# ContunityTestingRig.net
KiCad netlist of a schematic drawn in EAGLE
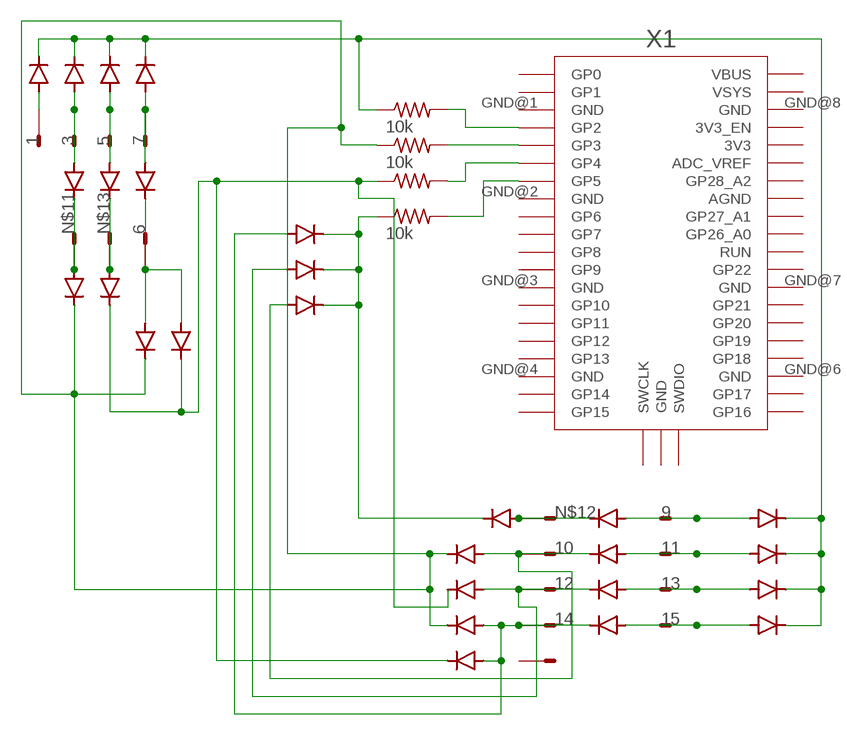
[diagram p0: schematic, sheet 1]

(export (version "E")
  (design (tool "Eeschema 10.0.6"))
  (components
    (comp (ref "D1")
      (value "SCHOTTKY")
      (footprint "eagle-import:MINI-SMA")
      (libsource (lib "eagle-import") (part "DIODE_SCHOTTKY_CDBM1100-G"))
    )
    (comp (ref "D2")
      (value "SCHOTTKY")
      (footprint "eagle-import:MINI-SMA")
      (libsource (lib "eagle-import") (part "DIODE_SCHOTTKY_CDBM1100-G"))
    )
    (comp (ref "D3")
      (value "SCHOTTKY")
      (footprint "eagle-import:MINI-SMA")
      (libsource (lib "eagle-import") (part "DIODE_SCHOTTKY_CDBM1100-G"))
    )
    (comp (ref "D4")
      (value "SCHOTTKY")
      (footprint "eagle-import:MINI-SMA")
      (libsource (lib "eagle-import") (part "DIODE_SCHOTTKY_CDBM1100-G"))
    )
    (comp (ref "D5")
      (value "SCHOTTKY")
      (footprint "eagle-import:MINI-SMA")
      (libsource (lib "eagle-import") (part "DIODE_SCHOTTKY_CDBM1100-G"))
    )
    (comp (ref "D6")
      (value "SCHOTTKY")
      (footprint "eagle-import:MINI-SMA")
      (libsource (lib "eagle-import") (part "DIODE_SCHOTTKY_CDBM1100-G"))
    )
    (comp (ref "D7")
      (value "SCHOTTKY")
      (footprint "eagle-import:MINI-SMA")
      (libsource (lib "eagle-import") (part "DIODE_SCHOTTKY_CDBM1100-G"))
    )
    (comp (ref "D8")
      (value "SCHOTTKY")
      (footprint "eagle-import:MINI-SMA")
      (libsource (lib "eagle-import") (part "DIODE_SCHOTTKY_CDBM1100-G"))
    )
    (comp (ref "D9")
      (value "SCHOTTKY")
      (footprint "eagle-import:MINI-SMA")
      (libsource (lib "eagle-import") (part "DIODE_SCHOTTKY_CDBM1100-G"))
    )
    (comp (ref "D10")
      (value "SCHOTTKY")
      (footprint "eagle-import:MINI-SMA")
      (libsource (lib "eagle-import") (part "DIODE_SCHOTTKY_CDBM1100-G"))
    )
    (comp (ref "D11")
      (value "SCHOTTKY")
      (footprint "eagle-import:MINI-SMA")
      (libsource (lib "eagle-import") (part "DIODE_SCHOTTKY_CDBM1100-G"))
    )
    (comp (ref "D12")
      (value "SCHOTTKY")
      (footprint "eagle-import:MINI-SMA")
      (libsource (lib "eagle-import") (part "DIODE_SCHOTTKY_CDBM1100-G"))
    )
    (comp (ref "D13")
      (value "SCHOTTKY")
      (footprint "eagle-import:MINI-SMA")
      (libsource (lib "eagle-import") (part "DIODE_SCHOTTKY_CDBM1100-G"))
    )
    (comp (ref "D14")
      (value "SCHOTTKY")
      (footprint "eagle-import:MINI-SMA")
      (libsource (lib "eagle-import") (part "DIODE_SCHOTTKY_CDBM1100-G"))
    )
    (comp (ref "D15")
      (value "SCHOTTKY")
      (footprint "eagle-import:MINI-SMA")
      (libsource (lib "eagle-import") (part "DIODE_SCHOTTKY_CDBM1100-G"))
    )
    (comp (ref "D16")
      (value "SCHOTTKY")
      (footprint "eagle-import:MINI-SMA")
      (libsource (lib "eagle-import") (part "DIODE_SCHOTTKY_CDBM1100-G"))
    )
    (comp (ref "D17")
      (value "SCHOTTKY")
      (footprint "eagle-import:MINI-SMA")
      (libsource (lib "eagle-import") (part "DIODE_SCHOTTKY_CDBM1100-G"))
    )
    (comp (ref "D18")
      (value "SCHOTTKY")
      (footprint "eagle-import:MINI-SMA")
      (libsource (lib "eagle-import") (part "DIODE_SCHOTTKY_CDBM1100-G"))
    )
    (comp (ref "D19")
      (value "SCHOTTKY")
      (footprint "eagle-import:MINI-SMA")
      (libsource (lib "eagle-import") (part "DIODE_SCHOTTKY_CDBM1100-G"))
    )
    (comp (ref "D20")
      (value "SCHOTTKY")
      (footprint "eagle-import:MINI-SMA")
      (libsource (lib "eagle-import") (part "DIODE_SCHOTTKY_CDBM1100-G"))
    )
    (comp (ref "D21")
      (value "SCHOTTKY")
      (footprint "eagle-import:MINI-SMA")
      (libsource (lib "eagle-import") (part "DIODE_SCHOTTKY_CDBM1100-G"))
    )
    (comp (ref "D22")
      (value "SCHOTTKY")
      (footprint "eagle-import:MINI-SMA")
      (libsource (lib "eagle-import") (part "DIODE_SCHOTTKY_CDBM1100-G"))
    )
    (comp (ref "D23")
      (value "SCHOTTKY")
      (footprint "eagle-import:MINI-SMA")
      (libsource (lib "eagle-import") (part "DIODE_SCHOTTKY_CDBM1100-G"))
    )
    (comp (ref "D24")
      (value "SCHOTTKY")
      (footprint "eagle-import:MINI-SMA")
      (libsource (lib "eagle-import") (part "DIODE_SCHOTTKY_CDBM1100-G"))
    )
    (comp (ref "D25")
      (value "SCHOTTKY")
      (footprint "eagle-import:MINI-SMA")
      (libsource (lib "eagle-import") (part "DIODE_SCHOTTKY_CDBM1100-G"))
    )
    (comp (ref "D26")
      (value "SCHOTTKY")
      (footprint "eagle-import:MINI-SMA")
      (libsource (lib "eagle-import") (part "DIODE_SCHOTTKY_CDBM1100-G"))
    )
    (comp (ref "D27")
      (value "SCHOTTKY")
      (footprint "eagle-import:MINI-SMA")
      (libsource (lib "eagle-import") (part "DIODE_SCHOTTKY_CDBM1100-G"))
    )
    (comp (ref "R1")
      (value "10k")
      (footprint "eagle-import:R1206FAB")
      (libsource (lib "eagle-import") (part "R1206FAB"))
    )
    (comp (ref "R2")
      (value "10k")
      (footprint "eagle-import:R1206FAB")
      (libsource (lib "eagle-import") (part "R1206FAB"))
    )
    (comp (ref "R3")
      (value "10k")
      (footprint "eagle-import:R1206FAB")
      (libsource (lib "eagle-import") (part "R1206FAB"))
    )
    (comp (ref "R4")
      (value "10k")
      (footprint "eagle-import:R1206FAB")
      (libsource (lib "eagle-import") (part "R1206FAB"))
    )
    (comp (ref "SV1")
      (value "16E")
      (footprint "eagle-import:16P")
      (libsource (lib "eagle-import") (part "16E"))
    )
    (comp (ref "X1")
      (value "RPI_PICO_IG-SMD")
      (footprint "eagle-import:RPI_PICO")
      (libsource (lib "eagle-import") (part "RPI_PICO_IG-SMD"))
    )
  )
  (nets
    (net (code "1") (name "/1") (class "Default")
      (node (ref "D1") (pin "KATHODE") (pinfunction "KATHODE_KATHODE") (pintype "bidirectional"))
      (node (ref "D13") (pin "KATHODE") (pinfunction "KATHODE_KATHODE") (pintype "bidirectional"))
      (node (ref "D14") (pin "KATHODE") (pinfunction "KATHODE_KATHODE") (pintype "bidirectional"))
      (node (ref "D15") (pin "KATHODE") (pinfunction "KATHODE_KATHODE") (pintype "bidirectional"))
      (node (ref "D16") (pin "KATHODE") (pinfunction "KATHODE_KATHODE") (pintype "bidirectional"))
      (node (ref "D2") (pin "KATHODE") (pinfunction "KATHODE_KATHODE") (pintype "bidirectional"))
      (node (ref "D24") (pin "KATHODE") (pinfunction "KATHODE_KATHODE") (pintype "bidirectional"))
      (node (ref "D3") (pin "KATHODE") (pinfunction "KATHODE_KATHODE") (pintype "bidirectional"))
      (node (ref "R1") (pin "1") (pinfunction "1_1") (pintype "passive"))
    )
    (net (code "2") (name "/3") (class "Default")
      (node (ref "D1") (pin "ANODE") (pinfunction "ANODE_ANODE") (pintype "bidirectional"))
      (node (ref "D4") (pin "ANODE") (pinfunction "ANODE_ANODE") (pintype "bidirectional"))
      (node (ref "SV1") (pin "3") (pinfunction "S_3") (pintype "passive"))
    )
    (net (code "3") (name "/5") (class "Default")
      (node (ref "D2") (pin "ANODE") (pinfunction "ANODE_ANODE") (pintype "bidirectional"))
      (node (ref "D5") (pin "ANODE") (pinfunction "ANODE_ANODE") (pintype "bidirectional"))
      (node (ref "SV1") (pin "5") (pinfunction "S_5") (pintype "passive"))
    )
    (net (code "4") (name "/6") (class "Default")
      (node (ref "D6") (pin "KATHODE") (pinfunction "KATHODE_KATHODE") (pintype "bidirectional"))
      (node (ref "D7") (pin "ANODE") (pinfunction "ANODE_ANODE") (pintype "bidirectional"))
      (node (ref "D8") (pin "ANODE") (pinfunction "ANODE_ANODE") (pintype "bidirectional"))
      (node (ref "SV1") (pin "6") (pinfunction "S_6") (pintype "passive"))
    )
    (net (code "5") (name "/7") (class "Default")
      (node (ref "D3") (pin "ANODE") (pinfunction "ANODE_ANODE") (pintype "bidirectional"))
      (node (ref "D6") (pin "ANODE") (pinfunction "ANODE_ANODE") (pintype "bidirectional"))
      (node (ref "SV1") (pin "7") (pinfunction "S_7") (pintype "passive"))
    )
    (net (code "6") (name "/9") (class "Default")
      (node (ref "D13") (pin "ANODE") (pinfunction "ANODE_ANODE") (pintype "bidirectional"))
      (node (ref "D9") (pin "ANODE") (pinfunction "ANODE_ANODE") (pintype "bidirectional"))
      (node (ref "SV1") (pin "9") (pinfunction "S_9") (pintype "passive"))
    )
    (net (code "7") (name "/10") (class "Default")
      (node (ref "D10") (pin "KATHODE") (pinfunction "KATHODE_KATHODE") (pintype "bidirectional"))
      (node (ref "D17") (pin "ANODE") (pinfunction "ANODE_ANODE") (pintype "bidirectional"))
      (node (ref "D23") (pin "ANODE") (pinfunction "ANODE_ANODE") (pintype "bidirectional"))
      (node (ref "SV1") (pin "10") (pinfunction "S_10") (pintype "passive"))
    )
    (net (code "8") (name "/11") (class "Default")
      (node (ref "D10") (pin "ANODE") (pinfunction "ANODE_ANODE") (pintype "bidirectional"))
      (node (ref "D14") (pin "ANODE") (pinfunction "ANODE_ANODE") (pintype "bidirectional"))
      (node (ref "SV1") (pin "11") (pinfunction "S_11") (pintype "passive"))
    )
    (net (code "9") (name "/12") (class "Default")
      (node (ref "D11") (pin "KATHODE") (pinfunction "KATHODE_KATHODE") (pintype "bidirectional"))
      (node (ref "D19") (pin "ANODE") (pinfunction "ANODE_ANODE") (pintype "bidirectional"))
      (node (ref "D22") (pin "ANODE") (pinfunction "ANODE_ANODE") (pintype "bidirectional"))
      (node (ref "SV1") (pin "12") (pinfunction "S_12") (pintype "passive"))
    )
    (net (code "10") (name "/13") (class "Default")
      (node (ref "D11") (pin "ANODE") (pinfunction "ANODE_ANODE") (pintype "bidirectional"))
      (node (ref "D15") (pin "ANODE") (pinfunction "ANODE_ANODE") (pintype "bidirectional"))
      (node (ref "SV1") (pin "13") (pinfunction "S_13") (pintype "passive"))
    )
    (net (code "11") (name "/14") (class "Default")
      (node (ref "D12") (pin "KATHODE") (pinfunction "KATHODE_KATHODE") (pintype "bidirectional"))
      (node (ref "D18") (pin "ANODE") (pinfunction "ANODE_ANODE") (pintype "bidirectional"))
      (node (ref "D20") (pin "ANODE") (pinfunction "ANODE_ANODE") (pintype "bidirectional"))
      (node (ref "D21") (pin "ANODE") (pinfunction "ANODE_ANODE") (pintype "bidirectional"))
      (node (ref "SV1") (pin "14") (pinfunction "S_14") (pintype "passive"))
    )
    (net (code "12") (name "/15") (class "Default")
      (node (ref "D12") (pin "ANODE") (pinfunction "ANODE_ANODE") (pintype "bidirectional"))
      (node (ref "D16") (pin "ANODE") (pinfunction "ANODE_ANODE") (pintype "bidirectional"))
      (node (ref "SV1") (pin "15") (pinfunction "S_15") (pintype "passive"))
    )
    (net (code "13") (name "/N$11") (class "Default")
      (node (ref "D25") (pin "ANODE") (pinfunction "ANODE_ANODE") (pintype "bidirectional"))
      (node (ref "D4") (pin "KATHODE") (pinfunction "KATHODE_KATHODE") (pintype "bidirectional"))
      (node (ref "SV1") (pin "2") (pinfunction "S_2") (pintype "passive"))
    )
    (net (code "14") (name "/N$12") (class "Default")
      (node (ref "D26") (pin "ANODE") (pinfunction "ANODE_ANODE") (pintype "bidirectional"))
      (node (ref "D9") (pin "KATHODE") (pinfunction "KATHODE_KATHODE") (pintype "bidirectional"))
      (node (ref "SV1") (pin "8") (pinfunction "S_8") (pintype "passive"))
    )
    (net (code "15") (name "/N$13") (class "Default")
      (node (ref "D27") (pin "ANODE") (pinfunction "ANODE_ANODE") (pintype "bidirectional"))
      (node (ref "D5") (pin "KATHODE") (pinfunction "KATHODE_KATHODE") (pintype "bidirectional"))
      (node (ref "SV1") (pin "4") (pinfunction "S_4") (pintype "passive"))
    )
    (net (code "16") (name "Net-(D17-PadKATHODE)") (class "Default")
      (node (ref "D17") (pin "KATHODE") (pinfunction "KATHODE_KATHODE") (pintype "bidirectional"))
      (node (ref "D18") (pin "KATHODE") (pinfunction "KATHODE_KATHODE") (pintype "bidirectional"))
      (node (ref "D25") (pin "KATHODE") (pinfunction "KATHODE_KATHODE") (pintype "bidirectional"))
      (node (ref "D7") (pin "KATHODE") (pinfunction "KATHODE_KATHODE") (pintype "bidirectional"))
      (node (ref "R2") (pin "1") (pinfunction "1_1") (pintype "passive"))
    )
    (net (code "17") (name "Net-(D19-PadKATHODE)") (class "Default")
      (node (ref "D19") (pin "KATHODE") (pinfunction "KATHODE_KATHODE") (pintype "bidirectional"))
      (node (ref "D20") (pin "KATHODE") (pinfunction "KATHODE_KATHODE") (pintype "bidirectional"))
      (node (ref "D27") (pin "KATHODE") (pinfunction "KATHODE_KATHODE") (pintype "bidirectional"))
      (node (ref "D8") (pin "KATHODE") (pinfunction "KATHODE_KATHODE") (pintype "bidirectional"))
      (node (ref "R3") (pin "1") (pinfunction "1_1") (pintype "passive"))
    )
    (net (code "18") (name "Net-(D21-PadKATHODE)") (class "Default")
      (node (ref "D21") (pin "KATHODE") (pinfunction "KATHODE_KATHODE") (pintype "bidirectional"))
      (node (ref "D22") (pin "KATHODE") (pinfunction "KATHODE_KATHODE") (pintype "bidirectional"))
      (node (ref "D23") (pin "KATHODE") (pinfunction "KATHODE_KATHODE") (pintype "bidirectional"))
      (node (ref "D26") (pin "KATHODE") (pinfunction "KATHODE_KATHODE") (pintype "bidirectional"))
      (node (ref "R4") (pin "1") (pinfunction "1_1") (pintype "passive"))
    )
    (net (code "19") (name "Net-(R1-Pad2)") (class "Default")
      (node (ref "R1") (pin "2") (pinfunction "2_2") (pintype "passive"))
      (node (ref "X1") (pin "GP2") (pinfunction "GP2_GP2") (pintype "bidirectional"))
    )
    (net (code "20") (name "Net-(R2-Pad2)") (class "Default")
      (node (ref "R2") (pin "2") (pinfunction "2_2") (pintype "passive"))
      (node (ref "X1") (pin "GP3") (pinfunction "GP3_GP3") (pintype "bidirectional"))
    )
    (net (code "21") (name "Net-(R3-Pad2)") (class "Default")
      (node (ref "R3") (pin "2") (pinfunction "2_2") (pintype "passive"))
      (node (ref "X1") (pin "GP4") (pinfunction "GP4_GP4") (pintype "bidirectional"))
    )
    (net (code "22") (name "Net-(R4-Pad2)") (class "Default")
      (node (ref "R4") (pin "2") (pinfunction "2_2") (pintype "passive"))
      (node (ref "X1") (pin "GP5") (pinfunction "GP5_GP5") (pintype "bidirectional"))
    )
    (net (code "23") (name "Net-(SV1A-S)") (class "Default")
      (node (ref "D24") (pin "ANODE") (pinfunction "ANODE_ANODE") (pintype "bidirectional"))
      (node (ref "SV1") (pin "1") (pinfunction "S_1") (pintype "passive"))
    )
    (net (code "24") (name "unconnected-(SV1H-S-Pad16)") (class "Default")
      (node (ref "SV1") (pin "16") (pinfunction "S_16") (pintype "passive"))
    )
    (net (code "25") (name "unconnected-(X1-GND-PadGND@1)") (class "Default")
      (node (ref "X1") (pin "GND@1") (pinfunction "GND_GND@1") (pintype "bidirectional"))
    )
    (net (code "26") (name "unconnected-(X1-GND-PadGND@2)") (class "Default")
      (node (ref "X1") (pin "GND@2") (pinfunction "GND_GND@2") (pintype "bidirectional"))
    )
    (net (code "27") (name "unconnected-(X1-GND-PadGND@3)") (class "Default")
      (node (ref "X1") (pin "GND@3") (pinfunction "GND_GND@3") (pintype "bidirectional"))
    )
    (net (code "28") (name "unconnected-(X1-GND-PadGND@4)") (class "Default")
      (node (ref "X1") (pin "GND@4") (pinfunction "GND_GND@4") (pintype "bidirectional"))
    )
    (net (code "29") (name "unconnected-(X1-GND-PadGND@5)") (class "Default")
      (node (ref "X1") (pin "GND@5") (pinfunction "GND_GND@5") (pintype "bidirectional"))
    )
    (net (code "30") (name "unconnected-(X1-GND-PadGND@6)") (class "Default")
      (node (ref "X1") (pin "GND@6") (pinfunction "GND_GND@6") (pintype "bidirectional"))
    )
    (net (code "31") (name "unconnected-(X1-GND-PadGND@7)") (class "Default")
      (node (ref "X1") (pin "GND@7") (pinfunction "GND_GND@7") (pintype "bidirectional"))
    )
    (net (code "32") (name "unconnected-(X1-GND-PadGND@8)") (class "Default")
      (node (ref "X1") (pin "GND@8") (pinfunction "GND_GND@8") (pintype "bidirectional"))
    )
    (net (code "33") (name "unconnected-(X1-Pad3V3)") (class "Default")
      (node (ref "X1") (pin "3V3") (pinfunction "3V3_3V3") (pintype "bidirectional"))
    )
    (net (code "34") (name "unconnected-(X1-Pad3V3_EN)") (class "Default")
      (node (ref "X1") (pin "3V3_EN") (pinfunction "3V3_EN_3V3_EN") (pintype "bidirectional"))
    )
    (net (code "35") (name "unconnected-(X1-PadADC_VREF)") (class "Default")
      (node (ref "X1") (pin "ADC_VREF") (pinfunction "ADC_VREF_ADC_VREF") (pintype "bidirectional"))
    )
    (net (code "36") (name "unconnected-(X1-PadAGND)") (class "Default")
      (node (ref "X1") (pin "AGND") (pinfunction "AGND_AGND") (pintype "bidirectional"))
    )
    (net (code "37") (name "unconnected-(X1-PadGP0)") (class "Default")
      (node (ref "X1") (pin "GP0") (pinfunction "GP0_GP0") (pintype "bidirectional"))
    )
    (net (code "38") (name "unconnected-(X1-PadGP1)") (class "Default")
      (node (ref "X1") (pin "GP1") (pinfunction "GP1_GP1") (pintype "bidirectional"))
    )
    (net (code "39") (name "unconnected-(X1-PadGP6)") (class "Default")
      (node (ref "X1") (pin "GP6") (pinfunction "GP6_GP6") (pintype "bidirectional"))
    )
    (net (code "40") (name "unconnected-(X1-PadGP7)") (class "Default")
      (node (ref "X1") (pin "GP7") (pinfunction "GP7_GP7") (pintype "bidirectional"))
    )
    (net (code "41") (name "unconnected-(X1-PadGP8)") (class "Default")
      (node (ref "X1") (pin "GP8") (pinfunction "GP8_GP8") (pintype "bidirectional"))
    )
    (net (code "42") (name "unconnected-(X1-PadGP9)") (class "Default")
      (node (ref "X1") (pin "GP9") (pinfunction "GP9_GP9") (pintype "bidirectional"))
    )
    (net (code "43") (name "unconnected-(X1-PadGP10)") (class "Default")
      (node (ref "X1") (pin "GP10") (pinfunction "GP10_GP10") (pintype "bidirectional"))
    )
    (net (code "44") (name "unconnected-(X1-PadGP11)") (class "Default")
      (node (ref "X1") (pin "GP11") (pinfunction "GP11_GP11") (pintype "bidirectional"))
    )
    (net (code "45") (name "unconnected-(X1-PadGP12)") (class "Default")
      (node (ref "X1") (pin "GP12") (pinfunction "GP12_GP12") (pintype "bidirectional"))
    )
    (net (code "46") (name "unconnected-(X1-PadGP13)") (class "Default")
      (node (ref "X1") (pin "GP13") (pinfunction "GP13_GP13") (pintype "bidirectional"))
    )
    (net (code "47") (name "unconnected-(X1-PadGP14)") (class "Default")
      (node (ref "X1") (pin "GP14") (pinfunction "GP14_GP14") (pintype "bidirectional"))
    )
    (net (code "48") (name "unconnected-(X1-PadGP15)") (class "Default")
      (node (ref "X1") (pin "GP15") (pinfunction "GP15_GP15") (pintype "bidirectional"))
    )
    (net (code "49") (name "unconnected-(X1-PadGP16)") (class "Default")
      (node (ref "X1") (pin "GP16") (pinfunction "GP16_GP16") (pintype "bidirectional"))
    )
    (net (code "50") (name "unconnected-(X1-PadGP17)") (class "Default")
      (node (ref "X1") (pin "GP17") (pinfunction "GP17_GP17") (pintype "bidirectional"))
    )
    (net (code "51") (name "unconnected-(X1-PadGP18)") (class "Default")
      (node (ref "X1") (pin "GP18") (pinfunction "GP18_GP18") (pintype "bidirectional"))
    )
    (net (code "52") (name "unconnected-(X1-PadGP19)") (class "Default")
      (node (ref "X1") (pin "GP19") (pinfunction "GP19_GP19") (pintype "bidirectional"))
    )
    (net (code "53") (name "unconnected-(X1-PadGP20)") (class "Default")
      (node (ref "X1") (pin "GP20") (pinfunction "GP20_GP20") (pintype "bidirectional"))
    )
    (net (code "54") (name "unconnected-(X1-PadGP21)") (class "Default")
      (node (ref "X1") (pin "GP21") (pinfunction "GP21_GP21") (pintype "bidirectional"))
    )
    (net (code "55") (name "unconnected-(X1-PadGP22)") (class "Default")
      (node (ref "X1") (pin "GP22") (pinfunction "GP22_GP22") (pintype "bidirectional"))
    )
    (net (code "56") (name "unconnected-(X1-PadGP26_A0)") (class "Default")
      (node (ref "X1") (pin "GP26_A0") (pinfunction "GP26_A0_GP26_A0") (pintype "bidirectional"))
    )
    (net (code "57") (name "unconnected-(X1-PadGP27_A1)") (class "Default")
      (node (ref "X1") (pin "GP27_A1") (pinfunction "GP27_A1_GP27_A1") (pintype "bidirectional"))
    )
    (net (code "58") (name "unconnected-(X1-PadGP28_A2)") (class "Default")
      (node (ref "X1") (pin "GP28_A2") (pinfunction "GP28_A2_GP28_A2") (pintype "bidirectional"))
    )
    (net (code "59") (name "unconnected-(X1-PadRUN)") (class "Default")
      (node (ref "X1") (pin "RUN") (pinfunction "RUN_RUN") (pintype "bidirectional"))
    )
    (net (code "60") (name "unconnected-(X1-PadSWCLK)") (class "Default")
      (node (ref "X1") (pin "SWCLK") (pinfunction "SWCLK_SWCLK") (pintype "bidirectional"))
    )
    (net (code "61") (name "unconnected-(X1-PadSWDIO)") (class "Default")
      (node (ref "X1") (pin "SWDIO") (pinfunction "SWDIO_SWDIO") (pintype "bidirectional"))
    )
    (net (code "62") (name "unconnected-(X1-PadVBUS)") (class "Default")
      (node (ref "X1") (pin "VBUS") (pinfunction "VBUS_VBUS") (pintype "bidirectional"))
    )
    (net (code "63") (name "unconnected-(X1-PadVSYS)") (class "Default")
      (node (ref "X1") (pin "VSYS") (pinfunction "VSYS_VSYS") (pintype "bidirectional"))
    )
  )
)
